# power.net
KiCad netlist of a schematic drawn in EAGLE
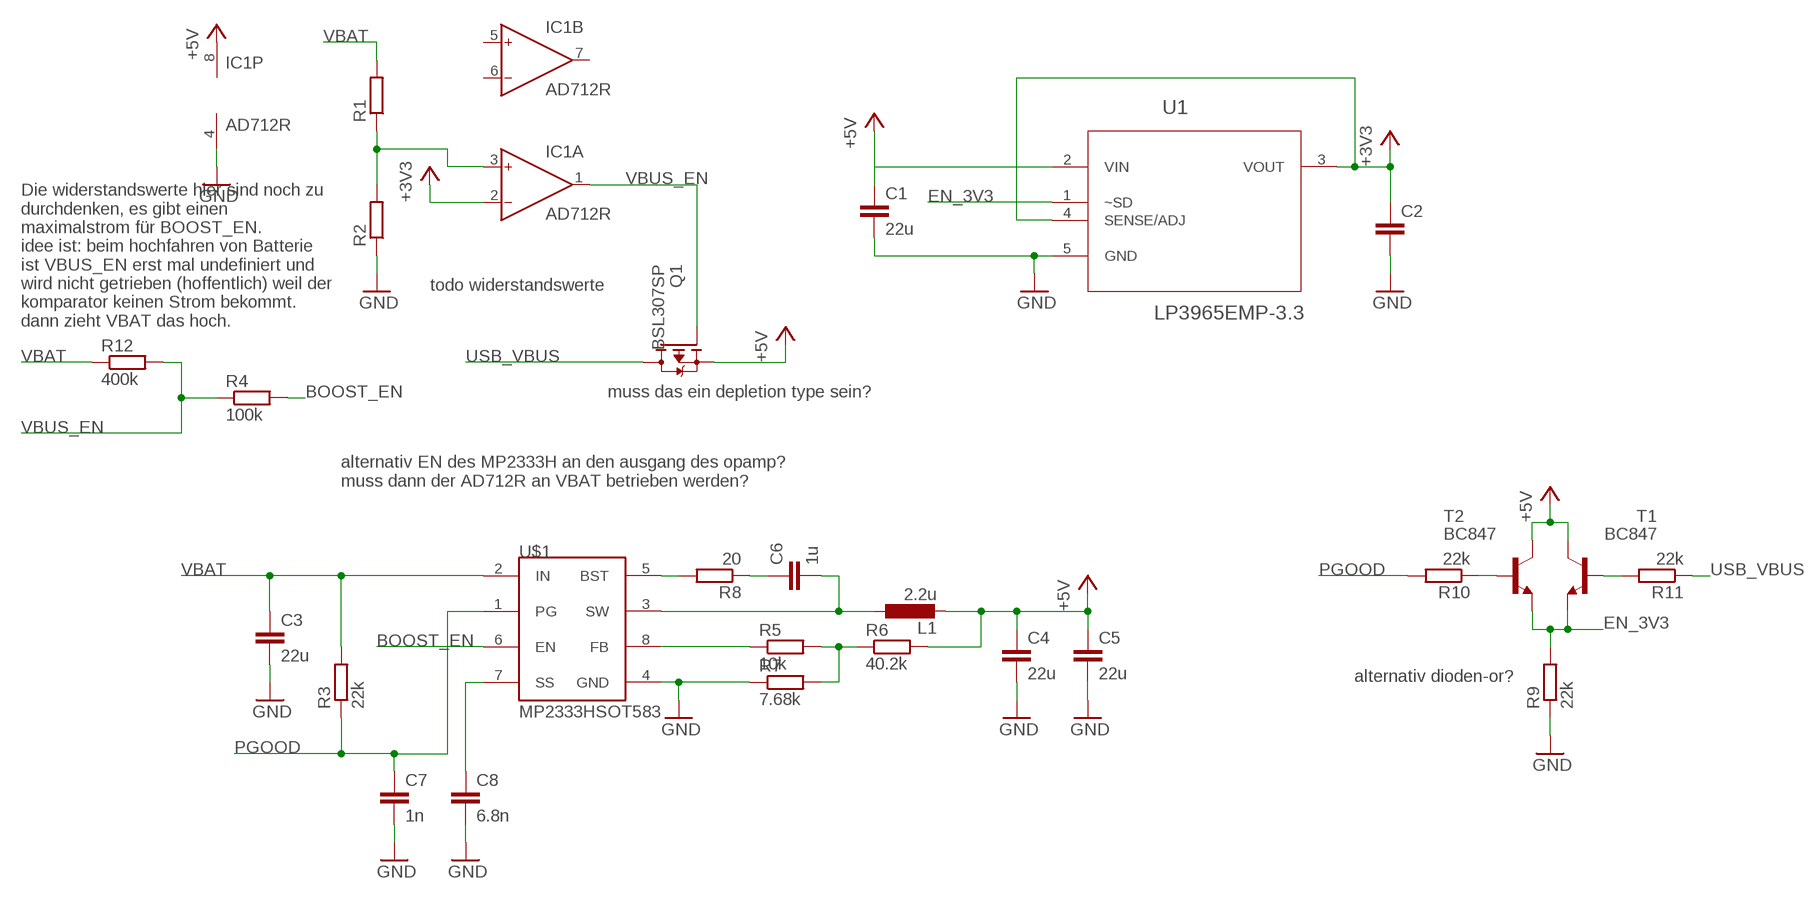
[diagram p0: schematic, sheet 1]

(export (version "E")
  (design (tool "Eeschema 10.0.6"))
  (components
    (comp (ref "C1")
      (value "22u")
      (footprint "eagle-import:C0603")
      (libsource (lib "eagle-import") (part "C-EUC0603"))
    )
    (comp (ref "C2")
      (value "C-EUC0603")
      (footprint "eagle-import:C0603")
      (libsource (lib "eagle-import") (part "C-EUC0603"))
    )
    (comp (ref "C3")
      (value "22u")
      (footprint "eagle-import:C0805")
      (libsource (lib "eagle-import") (part "C-EUC0805"))
    )
    (comp (ref "C4")
      (value "22u")
      (footprint "eagle-import:C0805")
      (libsource (lib "eagle-import") (part "C-EUC0805"))
    )
    (comp (ref "C5")
      (value "22u")
      (footprint "eagle-import:C0805")
      (libsource (lib "eagle-import") (part "C-EUC0805"))
    )
    (comp (ref "C6")
      (value "1u")
      (footprint "eagle-import:C0805")
      (libsource (lib "eagle-import") (part "C-EUC0805"))
    )
    (comp (ref "C7")
      (value "1n")
      (footprint "eagle-import:C0603")
      (libsource (lib "eagle-import") (part "C-EUC0603"))
    )
    (comp (ref "C8")
      (value "6.8n")
      (footprint "eagle-import:C0603")
      (libsource (lib "eagle-import") (part "C-EUC0603"))
    )
    (comp (ref "IC1")
      (value "AD712R")
      (footprint "eagle-import:SO8")
      (fields (field (name "MF") "ALTERA CORPORATION") (field (name "MPN") "AD712KRZ"))
      (libsource (lib "eagle-import") (part "AD712R"))
    )
    (comp (ref "L1")
      (value "2.2u")
      (footprint "eagle-import:PIS2816")
      (libsource (lib "eagle-import") (part "L-EUPIS2816"))
    )
    (comp (ref "Q1")
      (value "BSL307SP")
      (footprint "eagle-import:SC74_INFINEON")
      (libsource (lib "eagle-import") (part "BSL307SP"))
    )
    (comp (ref "R1")
      (value "R-EU_R0603")
      (footprint "eagle-import:R0603")
      (libsource (lib "eagle-import") (part "R-EU_R0603"))
    )
    (comp (ref "R2")
      (value "R-EU_R0603")
      (footprint "eagle-import:R0603")
      (libsource (lib "eagle-import") (part "R-EU_R0603"))
    )
    (comp (ref "R3")
      (value "22k")
      (footprint "eagle-import:R0603")
      (libsource (lib "eagle-import") (part "R-EU_R0603"))
    )
    (comp (ref "R4")
      (value "100k")
      (footprint "eagle-import:R0603")
      (libsource (lib "eagle-import") (part "R-EU_R0603"))
    )
    (comp (ref "R5")
      (value "10k")
      (footprint "eagle-import:R0603")
      (libsource (lib "eagle-import") (part "R-EU_R0603"))
    )
    (comp (ref "R6")
      (value "40.2k")
      (footprint "eagle-import:R0603")
      (libsource (lib "eagle-import") (part "R-EU_R0603"))
    )
    (comp (ref "R7")
      (value "7.68k")
      (footprint "eagle-import:R0603")
      (libsource (lib "eagle-import") (part "R-EU_R0603"))
    )
    (comp (ref "R8")
      (value "20")
      (footprint "eagle-import:R0603")
      (libsource (lib "eagle-import") (part "R-EU_R0603"))
    )
    (comp (ref "R9")
      (value "22k")
      (footprint "eagle-import:R0603")
      (libsource (lib "eagle-import") (part "R-EU_R0603"))
    )
    (comp (ref "R10")
      (value "22k")
      (footprint "eagle-import:R0603")
      (libsource (lib "eagle-import") (part "R-EU_R0603"))
    )
    (comp (ref "R11")
      (value "22k")
      (footprint "eagle-import:R0603")
      (libsource (lib "eagle-import") (part "R-EU_R0603"))
    )
    (comp (ref "R12")
      (value "400k")
      (footprint "eagle-import:R0603")
      (libsource (lib "eagle-import") (part "R-EU_R0603"))
    )
    (comp (ref "T1")
      (value "BC847")
      (footprint "eagle-import:SOT23")
      (libsource (lib "eagle-import") (part "BC847"))
    )
    (comp (ref "T2")
      (value "BC847")
      (footprint "eagle-import:SOT23")
      (libsource (lib "eagle-import") (part "BC847"))
    )
    (comp (ref "U$1")
      (value "MP2333HSOT583")
      (footprint "eagle-import:SOTFL50P175X60-8N")
      (libsource (lib "eagle-import") (part "MP2333HSOT583"))
    )
    (comp (ref "U1")
      (value "LP3965EMP-3.3")
      (footprint "eagle-import:SOT150P696X180-5N")
      (fields (field (name "MF") "Texas Instruments") (field (name "MP") "LP3965EMP-3.3/NOPB"))
      (libsource (lib "eagle-import") (part "LP3965EMP-3.3"))
    )
  )
  (nets
    (net (code "1") (name "+3V3") (class "Default")
      (node (ref "C2") (pin "1") (pinfunction "1_1") (pintype "passive"))
      (node (ref "IC1") (pin "2") (pinfunction "IN-_2") (pintype "input"))
      (node (ref "U1") (pin "3") (pinfunction "VOUT_3") (pintype "output"))
      (node (ref "U1") (pin "4") (pinfunction "SENSE/ADJ_4") (pintype "input"))
    )
    (net (code "2") (name "+5V") (class "Default")
      (node (ref "C1") (pin "1") (pinfunction "1_1") (pintype "passive"))
      (node (ref "C4") (pin "1") (pinfunction "1_1") (pintype "passive"))
      (node (ref "C5") (pin "1") (pinfunction "1_1") (pintype "passive"))
      (node (ref "IC1") (pin "8") (pinfunction "V+_8") (pintype "power_in"))
      (node (ref "L1") (pin "2") (pinfunction "2_2") (pintype "passive"))
      (node (ref "Q1") (pin "4") (pinfunction "S_4") (pintype "passive"))
      (node (ref "R6") (pin "2") (pinfunction "2_2") (pintype "passive"))
      (node (ref "T1") (pin "3") (pinfunction "C_3") (pintype "passive"))
      (node (ref "T2") (pin "3") (pinfunction "C_3") (pintype "passive"))
      (node (ref "U1") (pin "2") (pinfunction "VIN_2") (pintype "power_in"))
    )
    (net (code "3") (name "BOOST_EN") (class "Default")
      (node (ref "R4") (pin "2") (pinfunction "2_2") (pintype "passive"))
      (node (ref "U$1") (pin "6") (pinfunction "EN_6") (pintype "input"))
    )
    (net (code "4") (name "EN_3V3") (class "Default")
      (node (ref "R9") (pin "2") (pinfunction "2_2") (pintype "passive"))
      (node (ref "T1") (pin "2") (pinfunction "E_2") (pintype "passive"))
      (node (ref "T2") (pin "2") (pinfunction "E_2") (pintype "passive"))
      (node (ref "U1") (pin "1") (pinfunction "~{SD}_1") (pintype "input"))
    )
    (net (code "5") (name "GND") (class "Default")
      (node (ref "C1") (pin "2") (pinfunction "2_2") (pintype "passive"))
      (node (ref "C2") (pin "2") (pinfunction "2_2") (pintype "passive"))
      (node (ref "C3") (pin "2") (pinfunction "2_2") (pintype "passive"))
      (node (ref "C4") (pin "2") (pinfunction "2_2") (pintype "passive"))
      (node (ref "C5") (pin "2") (pinfunction "2_2") (pintype "passive"))
      (node (ref "C7") (pin "2") (pinfunction "2_2") (pintype "passive"))
      (node (ref "C8") (pin "2") (pinfunction "2_2") (pintype "passive"))
      (node (ref "IC1") (pin "4") (pinfunction "V-_4") (pintype "power_in"))
      (node (ref "R2") (pin "1") (pinfunction "1_1") (pintype "passive"))
      (node (ref "R7") (pin "1") (pinfunction "1_1") (pintype "passive"))
      (node (ref "R9") (pin "1") (pinfunction "1_1") (pintype "passive"))
      (node (ref "U$1") (pin "4") (pinfunction "GND_4") (pintype "power_in"))
      (node (ref "U1") (pin "5") (pinfunction "GND_5") (pintype "passive"))
    )
    (net (code "6") (name "Net-(C6-Pad1)") (class "Default")
      (node (ref "C6") (pin "1") (pinfunction "1_1") (pintype "passive"))
      (node (ref "R8") (pin "1") (pinfunction "1_1") (pintype "passive"))
    )
    (net (code "7") (name "Net-(IC1A-IN+)") (class "Default")
      (node (ref "IC1") (pin "3") (pinfunction "IN+_3") (pintype "input"))
      (node (ref "R1") (pin "1") (pinfunction "1_1") (pintype "passive"))
      (node (ref "R2") (pin "2") (pinfunction "2_2") (pintype "passive"))
    )
    (net (code "8") (name "Net-(R5-Pad2)") (class "Default")
      (node (ref "R5") (pin "2") (pinfunction "2_2") (pintype "passive"))
      (node (ref "R6") (pin "1") (pinfunction "1_1") (pintype "passive"))
      (node (ref "R7") (pin "2") (pinfunction "2_2") (pintype "passive"))
    )
    (net (code "9") (name "Net-(T1-B)") (class "Default")
      (node (ref "R11") (pin "2") (pinfunction "2_2") (pintype "passive"))
      (node (ref "T1") (pin "1") (pinfunction "B_1") (pintype "passive"))
    )
    (net (code "10") (name "Net-(T2-B)") (class "Default")
      (node (ref "R10") (pin "1") (pinfunction "1_1") (pintype "passive"))
      (node (ref "T2") (pin "1") (pinfunction "B_1") (pintype "passive"))
    )
    (net (code "11") (name "Net-(U$1-BST)") (class "Default")
      (node (ref "R8") (pin "2") (pinfunction "2_2") (pintype "passive"))
      (node (ref "U$1") (pin "5") (pinfunction "BST_5") (pintype "passive"))
    )
    (net (code "12") (name "Net-(U$1-FB)") (class "Default")
      (node (ref "R5") (pin "1") (pinfunction "1_1") (pintype "passive"))
      (node (ref "U$1") (pin "8") (pinfunction "FB_8") (pintype "input"))
    )
    (net (code "13") (name "Net-(U$1-SS)") (class "Default")
      (node (ref "C8") (pin "1") (pinfunction "1_1") (pintype "passive"))
      (node (ref "U$1") (pin "7") (pinfunction "SS_7") (pintype "input"))
    )
    (net (code "14") (name "Net-(U$1-SW)") (class "Default")
      (node (ref "C6") (pin "2") (pinfunction "2_2") (pintype "passive"))
      (node (ref "L1") (pin "1") (pinfunction "1_1") (pintype "passive"))
      (node (ref "U$1") (pin "3") (pinfunction "SW_3") (pintype "passive"))
    )
    (net (code "15") (name "PGOOD") (class "Default")
      (node (ref "C7") (pin "1") (pinfunction "1_1") (pintype "passive"))
      (node (ref "R10") (pin "2") (pinfunction "2_2") (pintype "passive"))
      (node (ref "R3") (pin "1") (pinfunction "1_1") (pintype "passive"))
      (node (ref "U$1") (pin "1") (pinfunction "PG_1") (pintype "output"))
    )
    (net (code "16") (name "USB_VBUS") (class "Default")
      (node (ref "Q1") (pin "1") (pinfunction "D_1") (pintype "passive"))
      (node (ref "Q1") (pin "2") (pinfunction "D_2") (pintype "passive"))
      (node (ref "Q1") (pin "5") (pinfunction "D_5") (pintype "passive"))
      (node (ref "Q1") (pin "6") (pinfunction "D_6") (pintype "passive"))
      (node (ref "R11") (pin "1") (pinfunction "1_1") (pintype "passive"))
    )
    (net (code "17") (name "VBAT") (class "Default")
      (node (ref "C3") (pin "1") (pinfunction "1_1") (pintype "passive"))
      (node (ref "R1") (pin "2") (pinfunction "2_2") (pintype "passive"))
      (node (ref "R12") (pin "1") (pinfunction "1_1") (pintype "passive"))
      (node (ref "R3") (pin "2") (pinfunction "2_2") (pintype "passive"))
      (node (ref "U$1") (pin "2") (pinfunction "IN_2") (pintype "power_in"))
    )
    (net (code "18") (name "VBUS_EN") (class "Default")
      (node (ref "IC1") (pin "1") (pinfunction "OUT_1") (pintype "output"))
      (node (ref "Q1") (pin "3") (pinfunction "G_3") (pintype "passive"))
      (node (ref "R12") (pin "2") (pinfunction "2_2") (pintype "passive"))
      (node (ref "R4") (pin "1") (pinfunction "1_1") (pintype "passive"))
    )
    (net (code "19") (name "unconnected-(IC1B-IN+-Pad5)") (class "Default")
      (node (ref "IC1") (pin "5") (pinfunction "IN+_5") (pintype "input"))
    )
    (net (code "20") (name "unconnected-(IC1B-IN--Pad6)") (class "Default")
      (node (ref "IC1") (pin "6") (pinfunction "IN-_6") (pintype "input"))
    )
    (net (code "21") (name "unconnected-(IC1B-OUT-Pad7)") (class "Default")
      (node (ref "IC1") (pin "7") (pinfunction "OUT_7") (pintype "output"))
    )
  )
)
